# Watchdog.net
KiCad netlist of a schematic drawn in Altium Designer
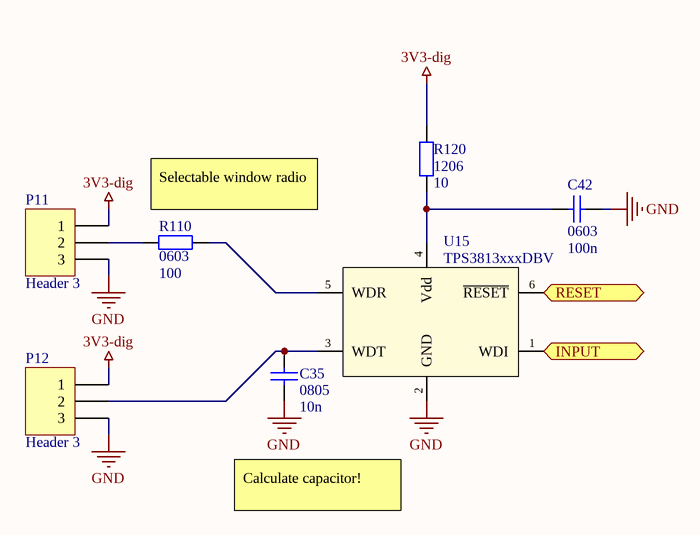
[diagram p0: Watchdog.SchDoc]

(export (version "E")
  (design (tool "Eeschema 10.0.6"))
  (components
    (comp (ref "C35")
      (value "0805")
      (footprint "SMD_Capacitor_0805")
      (description "Capacitor")
      (fields (field (name "ALTIUM_VALUE") "10n") (field (name "PUBLISHER") "Altium Limited"))
      (libsource (lib "Miscellaneous Devices") (part "Cap"))
    )
    (comp (ref "C42")
      (value "0603")
      (footprint "SMD_Capacitor_0603")
      (description "Capacitor")
      (fields (field (name "ALTIUM_VALUE") "100n") (field (name "PUBLISHER") "Altium Limited"))
      (libsource (lib "Miscellaneous Devices") (part "Cap"))
    )
    (comp (ref "P11")
      (value "Header 3")
      (footprint "HDR1X3")
      (description "Header, 3-Pin")
      (fields (field (name "PUBLISHER") "Altium Limited"))
      (libsource (lib "Miscellaneous Connectors") (part "Header 3"))
    )
    (comp (ref "P12")
      (value "Header 3")
      (footprint "HDR1X3")
      (description "Header, 3-Pin")
      (fields (field (name "PUBLISHER") "Altium Limited"))
      (libsource (lib "Miscellaneous Connectors") (part "Header 3"))
    )
    (comp (ref "R110")
      (value "0603")
      (footprint "SMD_Resistor_0603")
      (description "Resistor")
      (fields (field (name "ALTIUM_VALUE") "100") (field (name "PUBLISHER") "Altium Limited"))
      (libsource (lib "") (part "Res2_1"))
    )
    (comp (ref "R120")
      (value "1206")
      (footprint "SMD_Resistor_1206")
      (description "Resistor")
      (fields (field (name "ALTIUM_VALUE") "10") (field (name "PUBLISHER") "Altium Limited"))
      (libsource (lib "Miscellaneous Devices") (part "Res2"))
    )
    (comp (ref "U15")
      (value "TPS3813xxxDBV")
      (footprint "SOT23-6")
      (description "Processor Supervisory Circuits with Window-Watchdog.")
      (fields (field (name "MANUFACTURER") "Texas Instruments"))
      (libsource (lib "microcircuits_other-functions") (part "TPS3813xxxDBV"))
    )
  )
  (nets
    (net (code "1") (name "/INPUT") (class "Default")
      (node (ref "U15") (pin "1") (pinfunction "WDI_1") (pintype "passive"))
    )
    (net (code "2") (name "/RESET") (class "Default")
      (node (ref "U15") (pin "6") (pinfunction "~{RESET}_6") (pintype "passive"))
    )
    (net (code "3") (name "3V3-dig") (class "Default")
      (node (ref "P11") (pin "1") (pinfunction "1_1") (pintype "passive"))
      (node (ref "P12") (pin "1") (pinfunction "1_1") (pintype "passive"))
      (node (ref "R120") (pin "1") (pinfunction "1_1") (pintype "passive"))
    )
    (net (code "4") (name "GND") (class "Default")
      (node (ref "C35") (pin "1") (pinfunction "1_1") (pintype "passive"))
      (node (ref "C42") (pin "1") (pinfunction "1_1") (pintype "passive"))
      (node (ref "P11") (pin "3") (pinfunction "3_3") (pintype "passive"))
      (node (ref "P12") (pin "3") (pinfunction "3_3") (pintype "passive"))
      (node (ref "U15") (pin "2") (pinfunction "GND_2") (pintype "passive"))
    )
    (net (code "5") (name "Net-(P11-Pad2)") (class "Default")
      (node (ref "P11") (pin "2") (pinfunction "2_2") (pintype "passive"))
      (node (ref "R110") (pin "1") (pinfunction "1_1") (pintype "passive"))
    )
    (net (code "6") (name "Net-(U15-Vdd)") (class "Default")
      (node (ref "C42") (pin "2") (pinfunction "2_2") (pintype "passive"))
      (node (ref "R120") (pin "2") (pinfunction "2_2") (pintype "passive"))
      (node (ref "U15") (pin "4") (pinfunction "Vdd_4") (pintype "passive"))
    )
    (net (code "7") (name "Net-(U15-WDR)") (class "Default")
      (node (ref "R110") (pin "2") (pinfunction "2_2") (pintype "passive"))
      (node (ref "U15") (pin "5") (pinfunction "WDR_5") (pintype "passive"))
    )
    (net (code "8") (name "Net-(U15-WDT)") (class "Default")
      (node (ref "C35") (pin "2") (pinfunction "2_2") (pintype "passive"))
      (node (ref "P12") (pin "2") (pinfunction "2_2") (pintype "passive"))
      (node (ref "U15") (pin "3") (pinfunction "WDT_3") (pintype "passive"))
    )
  )
)
